# board_v3.net
KiCad netlist of a schematic drawn in EAGLE
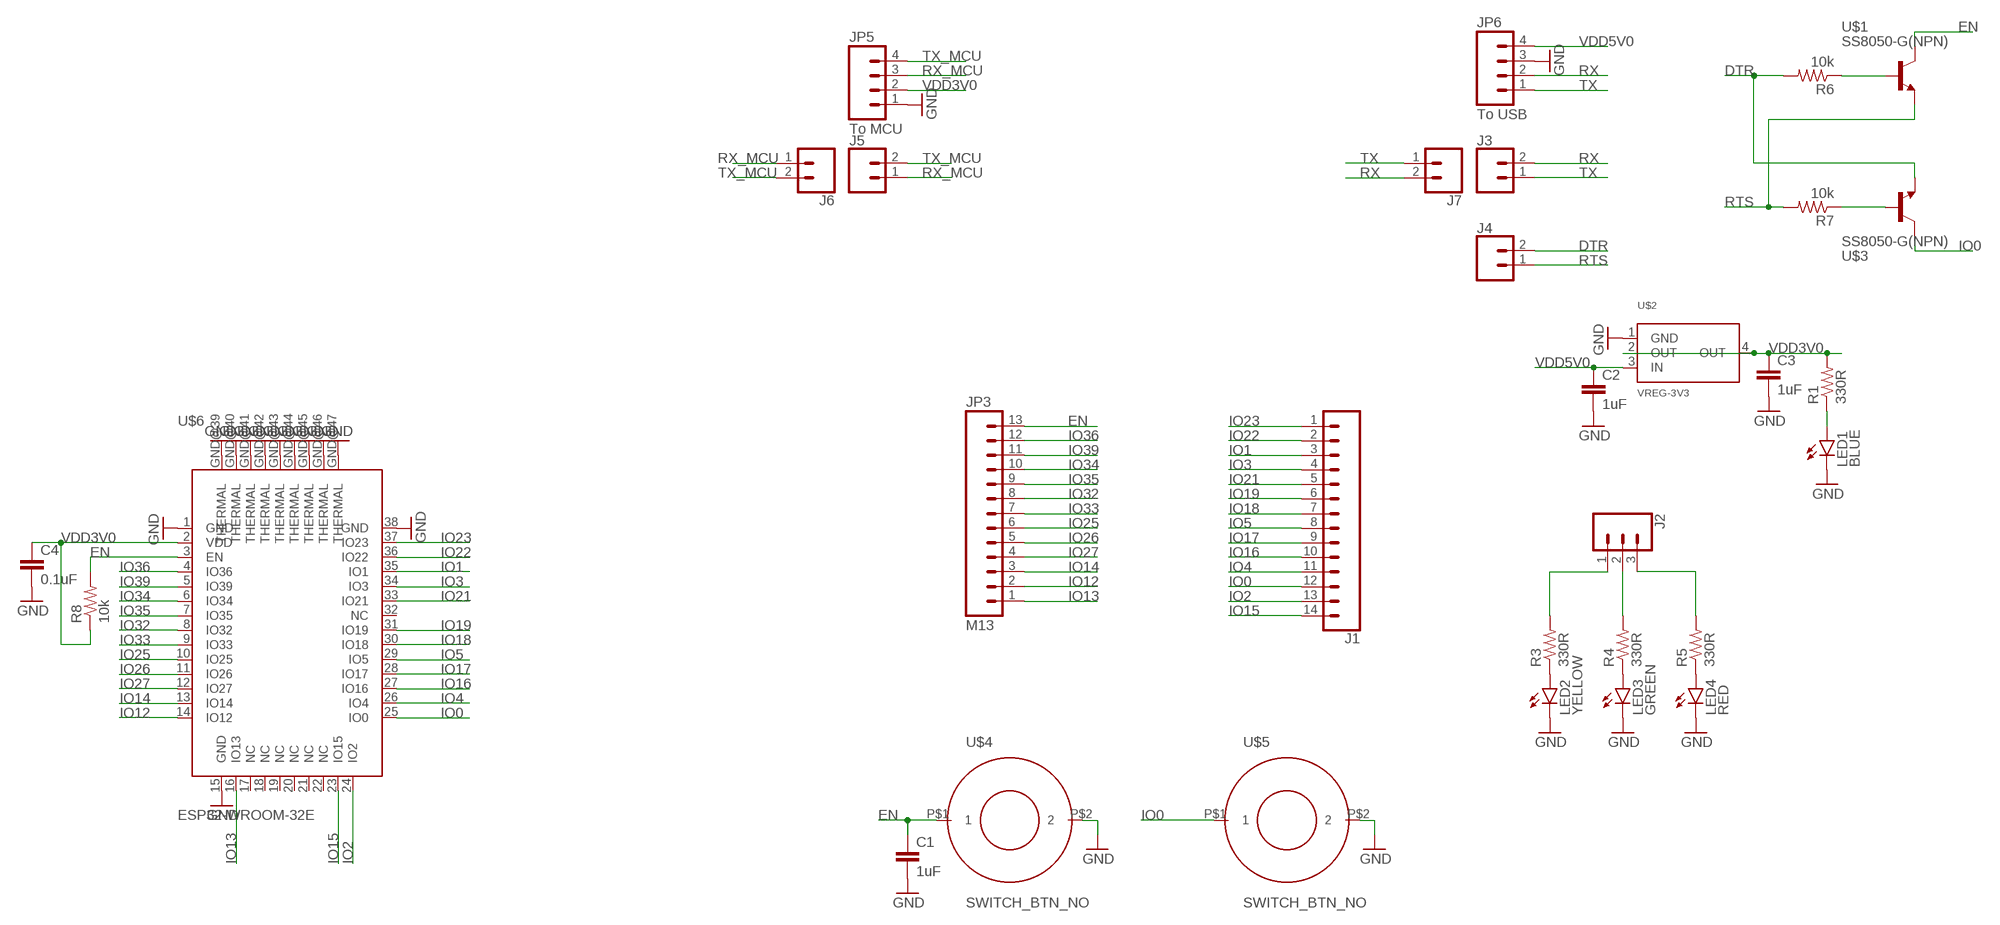
[diagram p0: schematic, sheet 1]

(export (version "E")
  (design (tool "Eeschema 10.0.6"))
  (components
    (comp (ref "C1")
      (value "1uF")
      (footprint "eagle-import:0805")
      (libsource (lib "eagle-import") (part "CAP"))
    )
    (comp (ref "C2")
      (value "1uF")
      (footprint "eagle-import:0805")
      (libsource (lib "eagle-import") (part "CAP"))
    )
    (comp (ref "C3")
      (value "1uF")
      (footprint "eagle-import:0805")
      (libsource (lib "eagle-import") (part "CAP"))
    )
    (comp (ref "C4")
      (value "0.1uF")
      (footprint "eagle-import:0805")
      (libsource (lib "eagle-import") (part "CAP"))
    )
    (comp (ref "J1")
      (value "CONN_14")
      (footprint "eagle-import:1X14")
      (libsource (lib "eagle-import") (part "CONN_14"))
    )
    (comp (ref "J2")
      (value "CONN_03")
      (footprint "eagle-import:1X03")
      (libsource (lib "eagle-import") (part "CONN_03"))
    )
    (comp (ref "J3")
      (value "CONN_02")
      (footprint "eagle-import:1X02")
      (libsource (lib "eagle-import") (part "CONN_02"))
    )
    (comp (ref "J4")
      (value "CONN_02")
      (footprint "eagle-import:1X02")
      (libsource (lib "eagle-import") (part "CONN_02"))
    )
    (comp (ref "J5")
      (value "CONN_02")
      (footprint "eagle-import:1X02")
      (libsource (lib "eagle-import") (part "CONN_02"))
    )
    (comp (ref "J6")
      (value "CONN_02")
      (footprint "eagle-import:1X02")
      (libsource (lib "eagle-import") (part "CONN_02"))
    )
    (comp (ref "J7")
      (value "CONN_02")
      (footprint "eagle-import:1X02")
      (libsource (lib "eagle-import") (part "CONN_02"))
    )
    (comp (ref "JP3")
      (value "M13")
      (footprint "eagle-import:1X13")
      (libsource (lib "eagle-import") (part "M13"))
    )
    (comp (ref "JP5")
      (value "To MCU")
      (footprint "eagle-import:1X04")
      (libsource (lib "eagle-import") (part "M04PTH"))
    )
    (comp (ref "JP6")
      (value "To USB")
      (footprint "eagle-import:1X04")
      (libsource (lib "eagle-import") (part "M04PTH"))
    )
    (comp (ref "LED1")
      (value "BLUE")
      (footprint "eagle-import:LED-0603")
      (libsource (lib "eagle-import") (part "LED0603"))
    )
    (comp (ref "LED2")
      (value "YELLOW")
      (footprint "eagle-import:LED-0603")
      (libsource (lib "eagle-import") (part "LED0603"))
    )
    (comp (ref "LED3")
      (value "GREEN")
      (footprint "eagle-import:LED-0603")
      (libsource (lib "eagle-import") (part "LED0603"))
    )
    (comp (ref "LED4")
      (value "RED")
      (footprint "eagle-import:LED-0603")
      (libsource (lib "eagle-import") (part "LED0603"))
    )
    (comp (ref "R1")
      (value "330R")
      (footprint "eagle-import:0805")
      (libsource (lib "eagle-import") (part "RES"))
    )
    (comp (ref "R3")
      (value "330R")
      (footprint "eagle-import:0805")
      (libsource (lib "eagle-import") (part "RES"))
    )
    (comp (ref "R4")
      (value "330R")
      (footprint "eagle-import:0805")
      (libsource (lib "eagle-import") (part "RES"))
    )
    (comp (ref "R5")
      (value "330R")
      (footprint "eagle-import:0805")
      (libsource (lib "eagle-import") (part "RES"))
    )
    (comp (ref "R6")
      (value "10k")
      (footprint "eagle-import:0805")
      (libsource (lib "eagle-import") (part "RES"))
    )
    (comp (ref "R7")
      (value "10k")
      (footprint "eagle-import:0805")
      (libsource (lib "eagle-import") (part "RES"))
    )
    (comp (ref "R8")
      (value "10k")
      (footprint "eagle-import:0805")
      (libsource (lib "eagle-import") (part "RES"))
    )
    (comp (ref "U$1")
      (value "SS8050-G(NPN)")
      (footprint "eagle-import:SOT-23(SS8050-G)")
      (libsource (lib "eagle-import") (part "SS8050-G(NPN)"))
    )
    (comp (ref "U$2")
      (value "VREG-3V3")
      (footprint "eagle-import:R-PDSO-G4_TI")
      (libsource (lib "eagle-import") (part "VREG-3V3"))
    )
    (comp (ref "U$3")
      (value "SS8050-G(NPN)")
      (footprint "eagle-import:SOT-23(SS8050-G)")
      (libsource (lib "eagle-import") (part "SS8050-G(NPN)"))
    )
    (comp (ref "U$4")
      (value "SWITCH_BTN_NO")
      (footprint "eagle-import:BTN_2")
      (libsource (lib "eagle-import") (part "SWITCH_BTN_NO"))
    )
    (comp (ref "U$5")
      (value "SWITCH_BTN_NO")
      (footprint "eagle-import:BTN_2")
      (libsource (lib "eagle-import") (part "SWITCH_BTN_NO"))
    )
    (comp (ref "U$6")
      (value "ESP32-WROOM-32E")
      (footprint "eagle-import:ESP32-WROOM-32E")
      (libsource (lib "eagle-import") (part "ESP32-WROOM-32E"))
    )
  )
  (nets
    (net (code "1") (name "/DTR") (class "Default")
      (node (ref "J4") (pin "2") (pinfunction "2_2") (pintype "passive"))
      (node (ref "R6") (pin "2") (pinfunction "2_2") (pintype "passive"))
      (node (ref "U$3") (pin "2") (pinfunction "E_2") (pintype "passive"))
    )
    (net (code "2") (name "/EN") (class "Default")
      (node (ref "C1") (pin "1") (pinfunction "1_1") (pintype "passive"))
      (node (ref "JP3") (pin "13") (pinfunction "13_13") (pintype "passive"))
      (node (ref "R8") (pin "2") (pinfunction "2_2") (pintype "passive"))
      (node (ref "U$1") (pin "3") (pinfunction "C_3") (pintype "passive"))
      (node (ref "U$4") (pin "P$1") (pinfunction "1_P$1") (pintype "bidirectional"))
      (node (ref "U$6") (pin "3") (pinfunction "EN_3") (pintype "bidirectional"))
    )
    (net (code "3") (name "/IO0") (class "Default")
      (node (ref "J1") (pin "12") (pinfunction "12_12") (pintype "passive"))
      (node (ref "U$3") (pin "3") (pinfunction "C_3") (pintype "passive"))
      (node (ref "U$5") (pin "P$1") (pinfunction "1_P$1") (pintype "bidirectional"))
      (node (ref "U$6") (pin "25") (pinfunction "IO0_25") (pintype "bidirectional"))
    )
    (net (code "4") (name "/IO1") (class "Default")
      (node (ref "J1") (pin "3") (pinfunction "3_3") (pintype "passive"))
      (node (ref "U$6") (pin "35") (pinfunction "IO1_35") (pintype "bidirectional"))
    )
    (net (code "5") (name "/IO2") (class "Default")
      (node (ref "J1") (pin "13") (pinfunction "13_13") (pintype "passive"))
      (node (ref "U$6") (pin "24") (pinfunction "IO2_24") (pintype "bidirectional"))
    )
    (net (code "6") (name "/IO3") (class "Default")
      (node (ref "J1") (pin "4") (pinfunction "4_4") (pintype "passive"))
      (node (ref "U$6") (pin "34") (pinfunction "IO3_34") (pintype "bidirectional"))
    )
    (net (code "7") (name "/IO4") (class "Default")
      (node (ref "J1") (pin "11") (pinfunction "11_11") (pintype "passive"))
      (node (ref "U$6") (pin "26") (pinfunction "IO4_26") (pintype "bidirectional"))
    )
    (net (code "8") (name "/IO5") (class "Default")
      (node (ref "J1") (pin "8") (pinfunction "8_8") (pintype "passive"))
      (node (ref "U$6") (pin "29") (pinfunction "IO5_29") (pintype "bidirectional"))
    )
    (net (code "9") (name "/IO12") (class "Default")
      (node (ref "JP3") (pin "2") (pinfunction "2_2") (pintype "passive"))
      (node (ref "U$6") (pin "14") (pinfunction "IO12_14") (pintype "bidirectional"))
    )
    (net (code "10") (name "/IO13") (class "Default")
      (node (ref "JP3") (pin "1") (pinfunction "1_1") (pintype "passive"))
      (node (ref "U$6") (pin "16") (pinfunction "IO13_16") (pintype "bidirectional"))
    )
    (net (code "11") (name "/IO14") (class "Default")
      (node (ref "JP3") (pin "3") (pinfunction "3_3") (pintype "passive"))
      (node (ref "U$6") (pin "13") (pinfunction "IO14_13") (pintype "bidirectional"))
    )
    (net (code "12") (name "/IO15") (class "Default")
      (node (ref "J1") (pin "14") (pinfunction "14_14") (pintype "passive"))
      (node (ref "U$6") (pin "23") (pinfunction "IO15_23") (pintype "bidirectional"))
    )
    (net (code "13") (name "/IO16") (class "Default")
      (node (ref "J1") (pin "10") (pinfunction "10_10") (pintype "passive"))
      (node (ref "U$6") (pin "27") (pinfunction "IO16_27") (pintype "bidirectional"))
    )
    (net (code "14") (name "/IO17") (class "Default")
      (node (ref "J1") (pin "9") (pinfunction "9_9") (pintype "passive"))
      (node (ref "U$6") (pin "28") (pinfunction "IO17_28") (pintype "bidirectional"))
    )
    (net (code "15") (name "/IO18") (class "Default")
      (node (ref "J1") (pin "7") (pinfunction "7_7") (pintype "passive"))
      (node (ref "U$6") (pin "30") (pinfunction "IO18_30") (pintype "bidirectional"))
    )
    (net (code "16") (name "/IO19") (class "Default")
      (node (ref "J1") (pin "6") (pinfunction "6_6") (pintype "passive"))
      (node (ref "U$6") (pin "31") (pinfunction "IO19_31") (pintype "bidirectional"))
    )
    (net (code "17") (name "/IO21") (class "Default")
      (node (ref "J1") (pin "5") (pinfunction "5_5") (pintype "passive"))
      (node (ref "U$6") (pin "33") (pinfunction "IO21_33") (pintype "bidirectional"))
    )
    (net (code "18") (name "/IO22") (class "Default")
      (node (ref "J1") (pin "2") (pinfunction "2_2") (pintype "passive"))
      (node (ref "U$6") (pin "36") (pinfunction "IO22_36") (pintype "bidirectional"))
    )
    (net (code "19") (name "/IO23") (class "Default")
      (node (ref "J1") (pin "1") (pinfunction "1_1") (pintype "passive"))
      (node (ref "U$6") (pin "37") (pinfunction "IO23_37") (pintype "bidirectional"))
    )
    (net (code "20") (name "/IO25") (class "Default")
      (node (ref "JP3") (pin "6") (pinfunction "6_6") (pintype "passive"))
      (node (ref "U$6") (pin "10") (pinfunction "IO25_10") (pintype "bidirectional"))
    )
    (net (code "21") (name "/IO26") (class "Default")
      (node (ref "JP3") (pin "5") (pinfunction "5_5") (pintype "passive"))
      (node (ref "U$6") (pin "11") (pinfunction "IO26_11") (pintype "bidirectional"))
    )
    (net (code "22") (name "/IO27") (class "Default")
      (node (ref "JP3") (pin "4") (pinfunction "4_4") (pintype "passive"))
      (node (ref "U$6") (pin "12") (pinfunction "IO27_12") (pintype "bidirectional"))
    )
    (net (code "23") (name "/IO32") (class "Default")
      (node (ref "JP3") (pin "8") (pinfunction "8_8") (pintype "passive"))
      (node (ref "U$6") (pin "8") (pinfunction "IO32_8") (pintype "bidirectional"))
    )
    (net (code "24") (name "/IO33") (class "Default")
      (node (ref "JP3") (pin "7") (pinfunction "7_7") (pintype "passive"))
      (node (ref "U$6") (pin "9") (pinfunction "IO33_9") (pintype "bidirectional"))
    )
    (net (code "25") (name "/IO34") (class "Default")
      (node (ref "JP3") (pin "10") (pinfunction "10_10") (pintype "passive"))
      (node (ref "U$6") (pin "6") (pinfunction "IO34_6") (pintype "bidirectional"))
    )
    (net (code "26") (name "/IO35") (class "Default")
      (node (ref "JP3") (pin "9") (pinfunction "9_9") (pintype "passive"))
      (node (ref "U$6") (pin "7") (pinfunction "IO35_7") (pintype "bidirectional"))
    )
    (net (code "27") (name "/IO36") (class "Default")
      (node (ref "JP3") (pin "12") (pinfunction "12_12") (pintype "passive"))
      (node (ref "U$6") (pin "4") (pinfunction "IO36_4") (pintype "bidirectional"))
    )
    (net (code "28") (name "/IO39") (class "Default")
      (node (ref "JP3") (pin "11") (pinfunction "11_11") (pintype "passive"))
      (node (ref "U$6") (pin "5") (pinfunction "IO39_5") (pintype "bidirectional"))
    )
    (net (code "29") (name "/RTS") (class "Default")
      (node (ref "J4") (pin "1") (pinfunction "1_1") (pintype "passive"))
      (node (ref "R7") (pin "2") (pinfunction "2_2") (pintype "passive"))
      (node (ref "U$1") (pin "2") (pinfunction "E_2") (pintype "passive"))
    )
    (net (code "30") (name "/RX") (class "Default")
      (node (ref "J3") (pin "2") (pinfunction "2_2") (pintype "passive"))
      (node (ref "J7") (pin "2") (pinfunction "2_2") (pintype "passive"))
      (node (ref "JP6") (pin "2") (pinfunction "2_2") (pintype "passive"))
    )
    (net (code "31") (name "/RX_MCU") (class "Default")
      (node (ref "J5") (pin "1") (pinfunction "1_1") (pintype "passive"))
      (node (ref "J6") (pin "1") (pinfunction "1_1") (pintype "passive"))
      (node (ref "JP5") (pin "3") (pinfunction "3_3") (pintype "passive"))
    )
    (net (code "32") (name "/TX") (class "Default")
      (node (ref "J3") (pin "1") (pinfunction "1_1") (pintype "passive"))
      (node (ref "J7") (pin "1") (pinfunction "1_1") (pintype "passive"))
      (node (ref "JP6") (pin "1") (pinfunction "1_1") (pintype "passive"))
    )
    (net (code "33") (name "/TX_MCU") (class "Default")
      (node (ref "J5") (pin "2") (pinfunction "2_2") (pintype "passive"))
      (node (ref "J6") (pin "2") (pinfunction "2_2") (pintype "passive"))
      (node (ref "JP5") (pin "4") (pinfunction "4_4") (pintype "passive"))
    )
    (net (code "34") (name "/VDD3V0") (class "Default")
      (node (ref "C3") (pin "1") (pinfunction "1_1") (pintype "passive"))
      (node (ref "C4") (pin "1") (pinfunction "1_1") (pintype "passive"))
      (node (ref "JP5") (pin "2") (pinfunction "2_2") (pintype "passive"))
      (node (ref "R1") (pin "2") (pinfunction "2_2") (pintype "passive"))
      (node (ref "R8") (pin "1") (pinfunction "1_1") (pintype "passive"))
      (node (ref "U$2") (pin "2") (pinfunction "OUT_2") (pintype "bidirectional"))
      (node (ref "U$2") (pin "4") (pinfunction "OUT_4") (pintype "bidirectional"))
      (node (ref "U$6") (pin "2") (pinfunction "VDD_2") (pintype "bidirectional"))
    )
    (net (code "35") (name "/VDD5V0") (class "Default")
      (node (ref "C2") (pin "1") (pinfunction "1_1") (pintype "passive"))
      (node (ref "JP6") (pin "4") (pinfunction "4_4") (pintype "passive"))
      (node (ref "U$2") (pin "3") (pinfunction "IN_3") (pintype "bidirectional"))
    )
    (net (code "36") (name "GND") (class "Default")
      (node (ref "C1") (pin "2") (pinfunction "2_2") (pintype "passive"))
      (node (ref "C2") (pin "2") (pinfunction "2_2") (pintype "passive"))
      (node (ref "C3") (pin "2") (pinfunction "2_2") (pintype "passive"))
      (node (ref "C4") (pin "2") (pinfunction "2_2") (pintype "passive"))
      (node (ref "JP5") (pin "1") (pinfunction "1_1") (pintype "passive"))
      (node (ref "JP6") (pin "3") (pinfunction "3_3") (pintype "passive"))
      (node (ref "LED1") (pin "C") (pinfunction "C_C") (pintype "passive"))
      (node (ref "LED2") (pin "C") (pinfunction "C_C") (pintype "passive"))
      (node (ref "LED3") (pin "C") (pinfunction "C_C") (pintype "passive"))
      (node (ref "LED4") (pin "C") (pinfunction "C_C") (pintype "passive"))
      (node (ref "U$2") (pin "1") (pinfunction "GND_1") (pintype "bidirectional"))
      (node (ref "U$4") (pin "P$2") (pinfunction "2_P$2") (pintype "bidirectional"))
      (node (ref "U$5") (pin "P$2") (pinfunction "2_P$2") (pintype "bidirectional"))
      (node (ref "U$6") (pin "1") (pinfunction "GND_1") (pintype "bidirectional"))
      (node (ref "U$6") (pin "15") (pinfunction "GND_15") (pintype "bidirectional"))
      (node (ref "U$6") (pin "38") (pinfunction "GND_38") (pintype "bidirectional"))
      (node (ref "U$6") (pin "GND@39") (pinfunction "THERMAL_GND@39") (pintype "bidirectional"))
      (node (ref "U$6") (pin "GND@40") (pinfunction "THERMAL_GND@40") (pintype "bidirectional"))
      (node (ref "U$6") (pin "GND@41") (pinfunction "THERMAL_GND@41") (pintype "bidirectional"))
      (node (ref "U$6") (pin "GND@42") (pinfunction "THERMAL_GND@42") (pintype "bidirectional"))
      (node (ref "U$6") (pin "GND@43") (pinfunction "THERMAL_GND@43") (pintype "bidirectional"))
      (node (ref "U$6") (pin "GND@44") (pinfunction "THERMAL_GND@44") (pintype "bidirectional"))
      (node (ref "U$6") (pin "GND@45") (pinfunction "THERMAL_GND@45") (pintype "bidirectional"))
      (node (ref "U$6") (pin "GND@46") (pinfunction "THERMAL_GND@46") (pintype "bidirectional"))
      (node (ref "U$6") (pin "GND@47") (pinfunction "THERMAL_GND@47") (pintype "bidirectional"))
    )
    (net (code "37") (name "Net-(J2-Pad1)") (class "Default")
      (node (ref "J2") (pin "1") (pinfunction "1_1") (pintype "passive"))
      (node (ref "R3") (pin "2") (pinfunction "2_2") (pintype "passive"))
    )
    (net (code "38") (name "Net-(J2-Pad2)") (class "Default")
      (node (ref "J2") (pin "2") (pinfunction "2_2") (pintype "passive"))
      (node (ref "R4") (pin "2") (pinfunction "2_2") (pintype "passive"))
    )
    (net (code "39") (name "Net-(J2-Pad3)") (class "Default")
      (node (ref "J2") (pin "3") (pinfunction "3_3") (pintype "passive"))
      (node (ref "R5") (pin "2") (pinfunction "2_2") (pintype "passive"))
    )
    (net (code "40") (name "Net-(LED1-PadA)") (class "Default")
      (node (ref "LED1") (pin "A") (pinfunction "A_A") (pintype "passive"))
      (node (ref "R1") (pin "1") (pinfunction "1_1") (pintype "passive"))
    )
    (net (code "41") (name "Net-(LED2-PadA)") (class "Default")
      (node (ref "LED2") (pin "A") (pinfunction "A_A") (pintype "passive"))
      (node (ref "R3") (pin "1") (pinfunction "1_1") (pintype "passive"))
    )
    (net (code "42") (name "Net-(LED3-PadA)") (class "Default")
      (node (ref "LED3") (pin "A") (pinfunction "A_A") (pintype "passive"))
      (node (ref "R4") (pin "1") (pinfunction "1_1") (pintype "passive"))
    )
    (net (code "43") (name "Net-(LED4-PadA)") (class "Default")
      (node (ref "LED4") (pin "A") (pinfunction "A_A") (pintype "passive"))
      (node (ref "R5") (pin "1") (pinfunction "1_1") (pintype "passive"))
    )
    (net (code "44") (name "Net-(U$1-B)") (class "Default")
      (node (ref "R6") (pin "1") (pinfunction "1_1") (pintype "passive"))
      (node (ref "U$1") (pin "1") (pinfunction "B_1") (pintype "passive"))
    )
    (net (code "45") (name "Net-(U$3-B)") (class "Default")
      (node (ref "R7") (pin "1") (pinfunction "1_1") (pintype "passive"))
      (node (ref "U$3") (pin "1") (pinfunction "B_1") (pintype "passive"))
    )
    (net (code "46") (name "unconnected-(U$6-NC-Pad17)") (class "Default")
      (node (ref "U$6") (pin "17") (pinfunction "NC_17") (pintype "bidirectional"))
    )
    (net (code "47") (name "unconnected-(U$6-NC-Pad18)") (class "Default")
      (node (ref "U$6") (pin "18") (pinfunction "NC_18") (pintype "bidirectional"))
    )
    (net (code "48") (name "unconnected-(U$6-NC-Pad19)") (class "Default")
      (node (ref "U$6") (pin "19") (pinfunction "NC_19") (pintype "bidirectional"))
    )
    (net (code "49") (name "unconnected-(U$6-NC-Pad20)") (class "Default")
      (node (ref "U$6") (pin "20") (pinfunction "NC_20") (pintype "bidirectional"))
    )
    (net (code "50") (name "unconnected-(U$6-NC-Pad21)") (class "Default")
      (node (ref "U$6") (pin "21") (pinfunction "NC_21") (pintype "bidirectional"))
    )
    (net (code "51") (name "unconnected-(U$6-NC-Pad22)") (class "Default")
      (node (ref "U$6") (pin "22") (pinfunction "NC_22") (pintype "bidirectional"))
    )
    (net (code "52") (name "unconnected-(U$6-NC-Pad32)") (class "Default")
      (node (ref "U$6") (pin "32") (pinfunction "NC_32") (pintype "bidirectional"))
    )
  )
)
